# 4_cyber60-mxhs_periferals.net
KiCad netlist of a schematic drawn in Altium Designer
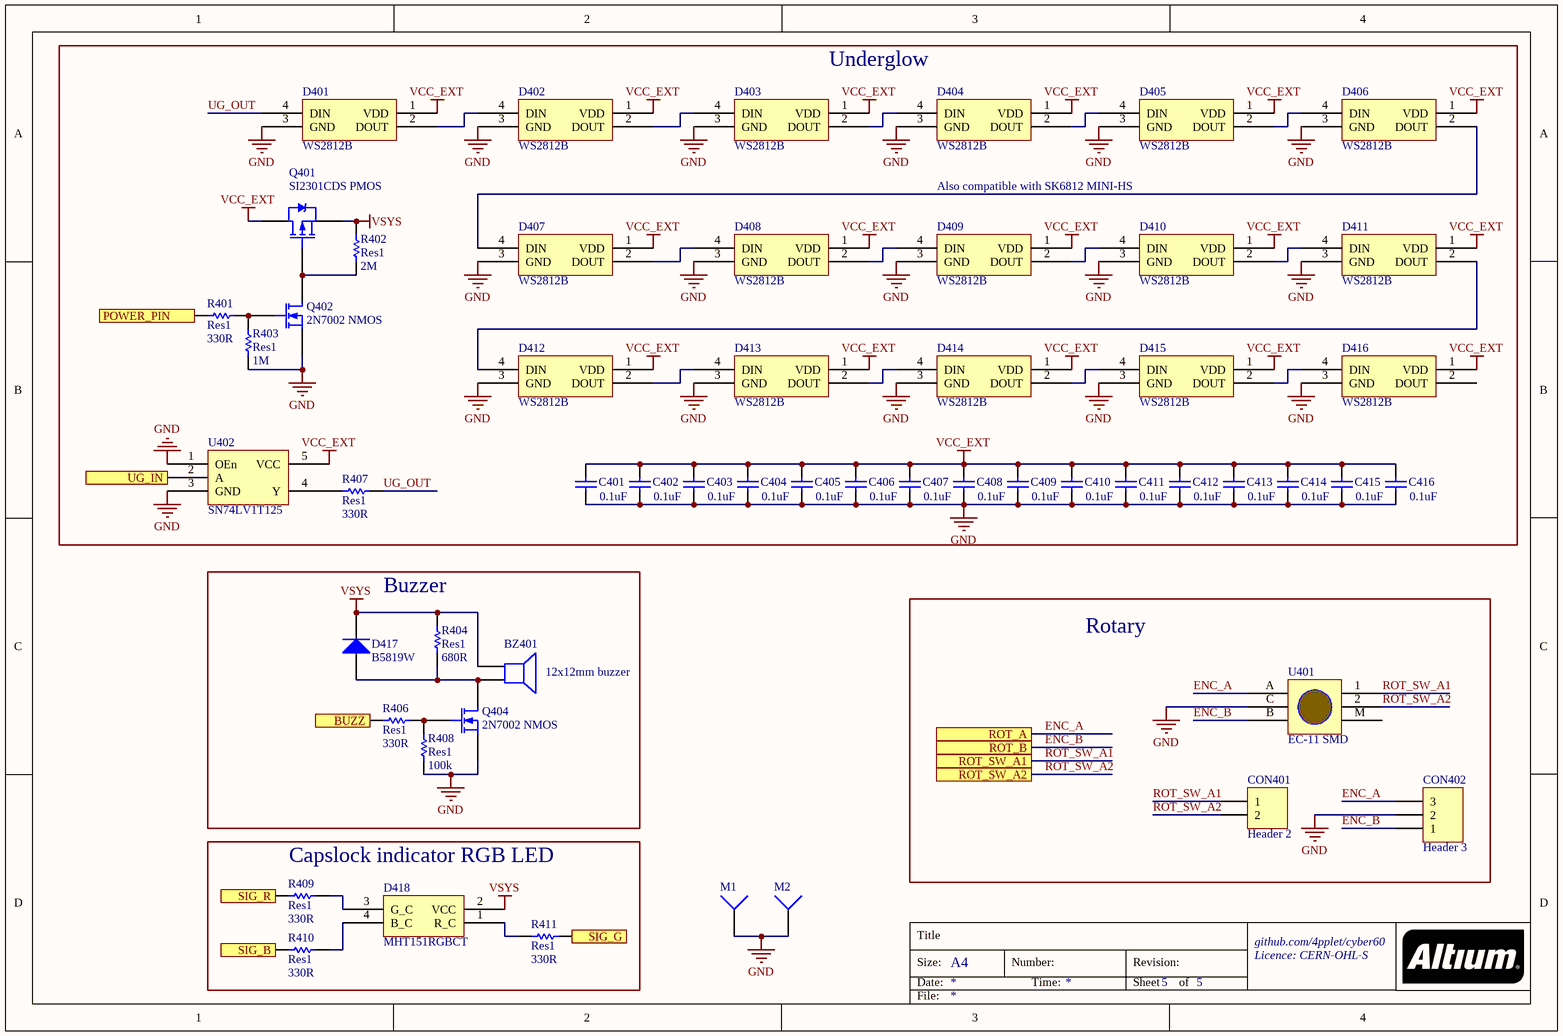
[diagram p0: 4_cyber60-mxhs_periferals.SchDoc]

(export (version "E")
  (design (tool "Eeschema 10.0.6"))
  (components
    (comp (ref "BZ401")
      (value "12x12mm buzzer")
      (footprint "buzzer 12x12")
      (description "Loudspeaker")
      (fields (field (name "LCSC PART #") "C409829") (field (name "MRF.PART") "YS-SBZ1230"))
      (libsource (lib "Miscellaneous Devices") (part "Speaker"))
    )
    (comp (ref "C401")
      (value "0.1uF")
      (footprint "C0603[1608]")
      (description "Capacitor")
      (fields (field (name "MFG") "KEMET") (field (name "LCSC PART #") "C14663"))
      (libsource (lib "Miscellaneous Devices") (part "Cap"))
    )
    (comp (ref "C402")
      (value "0.1uF")
      (footprint "C0603[1608]")
      (description "Capacitor")
      (fields (field (name "MFG") "KEMET") (field (name "LCSC PART #") "C14663"))
      (libsource (lib "Miscellaneous Devices") (part "Cap"))
    )
    (comp (ref "C403")
      (value "0.1uF")
      (footprint "C0603[1608]")
      (description "Capacitor")
      (fields (field (name "MFG") "KEMET") (field (name "LCSC PART #") "C14663"))
      (libsource (lib "Miscellaneous Devices") (part "Cap"))
    )
    (comp (ref "C404")
      (value "0.1uF")
      (footprint "C0603[1608]")
      (description "Capacitor")
      (fields (field (name "MFG") "KEMET") (field (name "LCSC PART #") "C14663"))
      (libsource (lib "Miscellaneous Devices") (part "Cap"))
    )
    (comp (ref "C405")
      (value "0.1uF")
      (footprint "C0603[1608]")
      (description "Capacitor")
      (fields (field (name "MFG") "KEMET") (field (name "LCSC PART #") "C14663"))
      (libsource (lib "Miscellaneous Devices") (part "Cap"))
    )
    (comp (ref "C406")
      (value "0.1uF")
      (footprint "C0603[1608]")
      (description "Capacitor")
      (fields (field (name "MFG") "KEMET") (field (name "LCSC PART #") "C14663"))
      (libsource (lib "Miscellaneous Devices") (part "Cap"))
    )
    (comp (ref "C407")
      (value "0.1uF")
      (footprint "C0603[1608]")
      (description "Capacitor")
      (fields (field (name "MFG") "KEMET") (field (name "LCSC PART #") "C14663"))
      (libsource (lib "Miscellaneous Devices") (part "Cap"))
    )
    (comp (ref "C408")
      (value "0.1uF")
      (footprint "C0603[1608]")
      (description "Capacitor")
      (fields (field (name "MFG") "KEMET") (field (name "LCSC PART #") "C14663"))
      (libsource (lib "Miscellaneous Devices") (part "Cap"))
    )
    (comp (ref "C409")
      (value "0.1uF")
      (footprint "C0603[1608]")
      (description "Capacitor")
      (fields (field (name "MFG") "KEMET") (field (name "LCSC PART #") "C14663"))
      (libsource (lib "Miscellaneous Devices") (part "Cap"))
    )
    (comp (ref "C410")
      (value "0.1uF")
      (footprint "C0603[1608]")
      (description "Capacitor")
      (fields (field (name "MFG") "KEMET") (field (name "LCSC PART #") "C14663"))
      (libsource (lib "Miscellaneous Devices") (part "Cap"))
    )
    (comp (ref "C411")
      (value "0.1uF")
      (footprint "C0603[1608]")
      (description "Capacitor")
      (fields (field (name "MFG") "KEMET") (field (name "LCSC PART #") "C14663"))
      (libsource (lib "Miscellaneous Devices") (part "Cap"))
    )
    (comp (ref "C412")
      (value "0.1uF")
      (footprint "C0603[1608]")
      (description "Capacitor")
      (fields (field (name "MFG") "KEMET") (field (name "LCSC PART #") "C14663"))
      (libsource (lib "Miscellaneous Devices") (part "Cap"))
    )
    (comp (ref "C413")
      (value "0.1uF")
      (footprint "C0603[1608]")
      (description "Capacitor")
      (fields (field (name "MFG") "KEMET") (field (name "LCSC PART #") "C14663"))
      (libsource (lib "Miscellaneous Devices") (part "Cap"))
    )
    (comp (ref "C414")
      (value "0.1uF")
      (footprint "C0603[1608]")
      (description "Capacitor")
      (fields (field (name "MFG") "KEMET") (field (name "LCSC PART #") "C14663"))
      (libsource (lib "Miscellaneous Devices") (part "Cap"))
    )
    (comp (ref "C415")
      (value "0.1uF")
      (footprint "C0603[1608]")
      (description "Capacitor")
      (fields (field (name "MFG") "KEMET") (field (name "LCSC PART #") "C14663"))
      (libsource (lib "Miscellaneous Devices") (part "Cap"))
    )
    (comp (ref "C416")
      (value "0.1uF")
      (footprint "C0603[1608]")
      (description "Capacitor")
      (fields (field (name "MFG") "KEMET") (field (name "LCSC PART #") "C14663"))
      (libsource (lib "Miscellaneous Devices") (part "Cap"))
    )
    (comp (ref "CON401")
      (value "Header 2")
      (footprint "HDR1X2")
      (description "Header, 2-Pin")
      (libsource (lib "Miscellaneous Connectors") (part "Header 2"))
    )
    (comp (ref "CON402")
      (value "Header 3")
      (footprint "HDR1X3")
      (description "Header, 3-Pin")
      (libsource (lib "Miscellaneous Connectors") (part "Header 3"))
    )
    (comp (ref "D401")
      (value "WS2812B")
      (footprint "WS2812B - 2020")
      (fields (field (name "LCSC PART #") "C965556") (field (name "MRF.PART") "WS2812C-2020"))
      (libsource (lib "Keebs") (part "WS2812B"))
    )
    (comp (ref "D402")
      (value "WS2812B")
      (footprint "WS2812B - 2020")
      (fields (field (name "LCSC PART #") "C965556") (field (name "MRF.PART") "WS2812C-2020"))
      (libsource (lib "Keebs") (part "WS2812B"))
    )
    (comp (ref "D403")
      (value "WS2812B")
      (footprint "WS2812B - 2020")
      (fields (field (name "LCSC PART #") "C965556") (field (name "MRF.PART") "WS2812C-2020"))
      (libsource (lib "Keebs") (part "WS2812B"))
    )
    (comp (ref "D404")
      (value "WS2812B")
      (footprint "WS2812B - 2020")
      (fields (field (name "LCSC PART #") "C965556") (field (name "MRF.PART") "WS2812C-2020"))
      (libsource (lib "Keebs") (part "WS2812B"))
    )
    (comp (ref "D405")
      (value "WS2812B")
      (footprint "WS2812B - 2020")
      (fields (field (name "LCSC PART #") "C965556") (field (name "MRF.PART") "WS2812C-2020"))
      (libsource (lib "Keebs") (part "WS2812B"))
    )
    (comp (ref "D406")
      (value "WS2812B")
      (footprint "WS2812B - 2020")
      (fields (field (name "LCSC PART #") "C965556") (field (name "MRF.PART") "WS2812C-2020"))
      (libsource (lib "Keebs") (part "WS2812B"))
    )
    (comp (ref "D407")
      (value "WS2812B")
      (footprint "WS2812B - 2020")
      (fields (field (name "LCSC PART #") "C965556") (field (name "MRF.PART") "WS2812C-2020"))
      (libsource (lib "Keebs") (part "WS2812B"))
    )
    (comp (ref "D408")
      (value "WS2812B")
      (footprint "WS2812B - 2020")
      (fields (field (name "LCSC PART #") "C965556") (field (name "MRF.PART") "WS2812C-2020"))
      (libsource (lib "Keebs") (part "WS2812B"))
    )
    (comp (ref "D409")
      (value "WS2812B")
      (footprint "WS2812B - 2020")
      (fields (field (name "LCSC PART #") "C965556") (field (name "MRF.PART") "WS2812C-2020"))
      (libsource (lib "Keebs") (part "WS2812B"))
    )
    (comp (ref "D410")
      (value "WS2812B")
      (footprint "WS2812B - 2020")
      (fields (field (name "LCSC PART #") "C965556") (field (name "MRF.PART") "WS2812C-2020"))
      (libsource (lib "Keebs") (part "WS2812B"))
    )
    (comp (ref "D411")
      (value "WS2812B")
      (footprint "WS2812B - 2020")
      (fields (field (name "LCSC PART #") "C965556") (field (name "MRF.PART") "WS2812C-2020"))
      (libsource (lib "Keebs") (part "WS2812B"))
    )
    (comp (ref "D412")
      (value "WS2812B")
      (footprint "WS2812B - 2020")
      (fields (field (name "LCSC PART #") "C965556") (field (name "MRF.PART") "WS2812C-2020"))
      (libsource (lib "Keebs") (part "WS2812B"))
    )
    (comp (ref "D413")
      (value "WS2812B")
      (footprint "WS2812B - 2020")
      (fields (field (name "LCSC PART #") "C965556") (field (name "MRF.PART") "WS2812C-2020"))
      (libsource (lib "Keebs") (part "WS2812B"))
    )
    (comp (ref "D414")
      (value "WS2812B")
      (footprint "WS2812B - 2020")
      (fields (field (name "LCSC PART #") "C965556") (field (name "MRF.PART") "WS2812C-2020"))
      (libsource (lib "Keebs") (part "WS2812B"))
    )
    (comp (ref "D415")
      (value "WS2812B")
      (footprint "WS2812B - 2020")
      (fields (field (name "LCSC PART #") "C965556") (field (name "MRF.PART") "WS2812C-2020"))
      (libsource (lib "Keebs") (part "WS2812B"))
    )
    (comp (ref "D416")
      (value "WS2812B")
      (footprint "WS2812B - 2020")
      (fields (field (name "LCSC PART #") "C965556") (field (name "MRF.PART") "WS2812C-2020"))
      (libsource (lib "Keebs") (part "WS2812B"))
    )
    (comp (ref "D417")
      (value "B5819W")
      (footprint "SOD-123")
      (description "Default Diode")
      (fields (field (name "LCSC PART #") "C8598"))
      (libsource (lib "Miscellaneous Devices") (part "Diode"))
    )
    (comp (ref "D418")
      (value "MHT151RGBCT")
      (footprint "MHT151RGBCT")
      (fields (field (name "LCSC PART #") "C2802677") (field (name "MRF.PART") "E6CC1205RGBC3UDA"))
      (libsource (lib "Keebs") (part "MHT151RGBCT"))
    )
    (comp (ref "M1")
      (value "Socket")
      (footprint "mounting_hole")
      (fields (field (name "PUBLISHER") "Altium Limited"))
      (libsource (lib "Miscellaneous Connectors") (part "Socket"))
    )
    (comp (ref "M2")
      (value "Socket")
      (footprint "mounting_hole")
      (fields (field (name "PUBLISHER") "Altium Limited"))
      (libsource (lib "Miscellaneous Connectors") (part "Socket"))
    )
    (comp (ref "Q401")
      (value "SI2301CDS PMOS")
      (footprint "SOT-23-3")
      (description "P-Channel Power MOSFET")
      (fields (field (name "MRF.PART") "SI2301CDS-T1-GE3") (field (name "LCSC PART #") "C10487"))
      (libsource (lib "Miscellaneous Devices") (part "PMOS-2"))
    )
    (comp (ref "Q402")
      (value "2N7002 NMOS")
      (footprint "SOT-23-3")
      (description "N-Channel MOSFET")
      (fields (field (name "LCSC PART #") "C8545") (field (name "MRF.PART") "2N7002"))
      (libsource (lib "Miscellaneous Devices") (part "MOSFET-N"))
    )
    (comp (ref "Q404")
      (value "2N7002 NMOS")
      (footprint "SOT-23-3")
      (description "N-Channel MOSFET")
      (fields (field (name "LCSC PART #") "C8545") (field (name "MRF.PART") "2N7002"))
      (libsource (lib "Miscellaneous Devices") (part "MOSFET-N"))
    )
    (comp (ref "R401")
      (value "Res1")
      (footprint "R0603[1608]")
      (description "Resistor")
      (fields
        (field (name "ALTIUM_VALUE") "330R")
        (field (name "LCSC PART #") "C23138")
        (field (name "MRF.PART") "0603WAF3300T5E")
      )
      (libsource (lib "Miscellaneous Devices") (part "Res1"))
    )
    (comp (ref "R402")
      (value "Res1")
      (footprint "R0603[1608]")
      (description "Resistor")
      (fields
        (field (name "ALTIUM_VALUE") "2M")
        (field (name "MRF.PART") "0603WAF2004T5E")
        (field (name "LCSC PART #") "C22976")
      )
      (libsource (lib "Miscellaneous Devices") (part "Res1"))
    )
    (comp (ref "R403")
      (value "Res1")
      (footprint "R0603[1608]")
      (description "Resistor")
      (fields
        (field (name "ALTIUM_VALUE") "1M")
        (field (name "MRF.PART") "0603WAF1004T5E")
        (field (name "LCSC PART #") "C22935")
      )
      (libsource (lib "Miscellaneous Devices") (part "Res1"))
    )
    (comp (ref "R404")
      (value "Res1")
      (footprint "R0603[1608]")
      (description "Resistor")
      (fields
        (field (name "ALTIUM_VALUE") "680R")
        (field (name "MRF.PART") "0603WAF6800T5E")
        (field (name "LCSC PART #") "C23228")
      )
      (libsource (lib "Miscellaneous Devices") (part "Res1"))
    )
    (comp (ref "R406")
      (value "Res1")
      (footprint "R0603[1608]")
      (description "Resistor")
      (fields
        (field (name "ALTIUM_VALUE") "330R")
        (field (name "LCSC PART #") "C23138")
        (field (name "MRF.PART") "0603WAF3300T5E")
      )
      (libsource (lib "Miscellaneous Devices") (part "Res1"))
    )
    (comp (ref "R407")
      (value "Res1")
      (footprint "R0603[1608]")
      (description "Resistor")
      (fields
        (field (name "ALTIUM_VALUE") "330R")
        (field (name "LCSC PART #") "C23138")
        (field (name "MRF.PART") "0603WAF3300T5E")
      )
      (libsource (lib "Miscellaneous Devices") (part "Res1"))
    )
    (comp (ref "R408")
      (value "Res1")
      (footprint "R0603[1608]")
      (description "Resistor")
      (fields
        (field (name "ALTIUM_VALUE") "100k")
        (field (name "MRF.PART") "0603WAF1003T5E")
        (field (name "LCSC PART #") "C25803")
      )
      (libsource (lib "Miscellaneous Devices") (part "Res1"))
    )
    (comp (ref "R409")
      (value "Res1")
      (footprint "R0603[1608]")
      (description "Resistor")
      (fields
        (field (name "ALTIUM_VALUE") "330R")
        (field (name "LCSC PART #") "C23138")
        (field (name "MRF.PART") "0603WAF3300T5E")
      )
      (libsource (lib "Miscellaneous Devices") (part "Res1"))
    )
    (comp (ref "R410")
      (value "Res1")
      (footprint "R0603[1608]")
      (description "Resistor")
      (fields
        (field (name "ALTIUM_VALUE") "330R")
        (field (name "LCSC PART #") "C23138")
        (field (name "MRF.PART") "0603WAF3300T5E")
      )
      (libsource (lib "Miscellaneous Devices") (part "Res1"))
    )
    (comp (ref "R411")
      (value "Res1")
      (footprint "R0603[1608]")
      (description "Resistor")
      (fields
        (field (name "ALTIUM_VALUE") "330R")
        (field (name "LCSC PART #") "C23138")
        (field (name "MRF.PART") "0603WAF3300T5E")
      )
      (libsource (lib "Miscellaneous Devices") (part "Res1"))
    )
    (comp (ref "U401") (value "EC-11 SMD") (footprint "EC11-SMD") (libsource (lib "Keebs") (part "EC-11")))
    (comp (ref "U402")
      (value "SN74LV1T125")
      (footprint "SOT-23-5")
      (description "SN74LV1T125 or SN74LV1T34. Connect OE to GND")
      (fields (field (name "LCSC PART #") "C473338") (field (name "MRF.PART") "SN74LV1T125DBVR"))
      (libsource (lib "Keebs") (part "SN74LV1T125"))
    )
  )
  (nets
    (net (code "1") (name "/BUZZ") (class "Default")
      (node (ref "R406") (pin "2") (pinfunction "2_2") (pintype "passive"))
    )
    (net (code "2") (name "/ENC_A") (class "Default")
      (node (ref "CON402") (pin "3") (pinfunction "3_3") (pintype "passive"))
      (node (ref "U401") (pin "A") (pinfunction "B_A") (pintype "passive"))
    )
    (net (code "3") (name "/ENC_B") (class "Default")
      (node (ref "CON402") (pin "1") (pinfunction "1_1") (pintype "passive"))
      (node (ref "U401") (pin "B") (pinfunction "B_B") (pintype "passive"))
    )
    (net (code "4") (name "/POWER_PIN") (class "Default")
      (node (ref "R401") (pin "1") (pinfunction "1_1") (pintype "passive"))
    )
    (net (code "5") (name "/ROT_SW_A1") (class "Default")
      (node (ref "CON401") (pin "1") (pinfunction "1_1") (pintype "passive"))
      (node (ref "U401") (pin "1") (pinfunction "1_1") (pintype "passive"))
    )
    (net (code "6") (name "/ROT_SW_A2") (class "Default")
      (node (ref "CON401") (pin "2") (pinfunction "2_2") (pintype "passive"))
      (node (ref "U401") (pin "2") (pinfunction "2_2") (pintype "passive"))
    )
    (net (code "7") (name "/SIG_B") (class "Default")
      (node (ref "R410") (pin "2") (pinfunction "2_2") (pintype "passive"))
    )
    (net (code "8") (name "/SIG_G") (class "Default")
      (node (ref "R411") (pin "1") (pinfunction "1_1") (pintype "passive"))
    )
    (net (code "9") (name "/SIG_R") (class "Default")
      (node (ref "R409") (pin "2") (pinfunction "2_2") (pintype "passive"))
    )
    (net (code "10") (name "/UG_IN") (class "Default")
      (node (ref "U402") (pin "2") (pinfunction "A_2") (pintype "passive"))
    )
    (net (code "11") (name "/UG_OUT") (class "Default")
      (node (ref "D401") (pin "4") (pinfunction "DIN_4") (pintype "passive"))
      (node (ref "R407") (pin "1") (pinfunction "1_1") (pintype "passive"))
    )
    (net (code "12") (name "GND") (class "Default")
      (node (ref "C401") (pin "1") (pinfunction "1_1") (pintype "passive"))
      (node (ref "C402") (pin "1") (pinfunction "1_1") (pintype "passive"))
      (node (ref "C403") (pin "1") (pinfunction "1_1") (pintype "passive"))
      (node (ref "C404") (pin "1") (pinfunction "1_1") (pintype "passive"))
      (node (ref "C405") (pin "1") (pinfunction "1_1") (pintype "passive"))
      (node (ref "C406") (pin "1") (pinfunction "1_1") (pintype "passive"))
      (node (ref "C407") (pin "1") (pinfunction "1_1") (pintype "passive"))
      (node (ref "C408") (pin "1") (pinfunction "1_1") (pintype "passive"))
      (node (ref "C409") (pin "1") (pinfunction "1_1") (pintype "passive"))
      (node (ref "C410") (pin "1") (pinfunction "1_1") (pintype "passive"))
      (node (ref "C411") (pin "1") (pinfunction "1_1") (pintype "passive"))
      (node (ref "C412") (pin "1") (pinfunction "1_1") (pintype "passive"))
      (node (ref "C413") (pin "1") (pinfunction "1_1") (pintype "passive"))
      (node (ref "C414") (pin "1") (pinfunction "1_1") (pintype "passive"))
      (node (ref "C415") (pin "1") (pinfunction "1_1") (pintype "passive"))
      (node (ref "C416") (pin "1") (pinfunction "1_1") (pintype "passive"))
      (node (ref "CON402") (pin "2") (pinfunction "2_2") (pintype "passive"))
      (node (ref "D401") (pin "3") (pinfunction "GND_3") (pintype "passive"))
      (node (ref "D402") (pin "3") (pinfunction "GND_3") (pintype "passive"))
      (node (ref "D403") (pin "3") (pinfunction "GND_3") (pintype "passive"))
      (node (ref "D404") (pin "3") (pinfunction "GND_3") (pintype "passive"))
      (node (ref "D405") (pin "3") (pinfunction "GND_3") (pintype "passive"))
      (node (ref "D406") (pin "3") (pinfunction "GND_3") (pintype "passive"))
      (node (ref "D407") (pin "3") (pinfunction "GND_3") (pintype "passive"))
      (node (ref "D408") (pin "3") (pinfunction "GND_3") (pintype "passive"))
      (node (ref "D409") (pin "3") (pinfunction "GND_3") (pintype "passive"))
      (node (ref "D410") (pin "3") (pinfunction "GND_3") (pintype "passive"))
      (node (ref "D411") (pin "3") (pinfunction "GND_3") (pintype "passive"))
      (node (ref "D412") (pin "3") (pinfunction "GND_3") (pintype "passive"))
      (node (ref "D413") (pin "3") (pinfunction "GND_3") (pintype "passive"))
      (node (ref "D414") (pin "3") (pinfunction "GND_3") (pintype "passive"))
      (node (ref "D415") (pin "3") (pinfunction "GND_3") (pintype "passive"))
      (node (ref "D416") (pin "3") (pinfunction "GND_3") (pintype "passive"))
      (node (ref "M1") (pin "1") (pinfunction "1_1") (pintype "passive"))
      (node (ref "M2") (pin "1") (pinfunction "1_1") (pintype "passive"))
      (node (ref "Q402") (pin "2") (pinfunction "S_2") (pintype "passive"))
      (node (ref "Q404") (pin "2") (pinfunction "S_2") (pintype "passive"))
      (node (ref "R403") (pin "2") (pinfunction "2_2") (pintype "passive"))
      (node (ref "R408") (pin "2") (pinfunction "2_2") (pintype "passive"))
      (node (ref "U401") (pin "C") (pinfunction "C_C") (pintype "passive"))
      (node (ref "U402") (pin "1") (pinfunction "OEn_1") (pintype "passive"))
      (node (ref "U402") (pin "3") (pinfunction "GND_3") (pintype "passive"))
    )
    (net (code "13") (name "Net-(D401-DOUT)") (class "Default")
      (node (ref "D401") (pin "2") (pinfunction "DOUT_2") (pintype "passive"))
      (node (ref "D402") (pin "4") (pinfunction "DIN_4") (pintype "passive"))
    )
    (net (code "14") (name "Net-(D402-DOUT)") (class "Default")
      (node (ref "D402") (pin "2") (pinfunction "DOUT_2") (pintype "passive"))
      (node (ref "D403") (pin "4") (pinfunction "DIN_4") (pintype "passive"))
    )
    (net (code "15") (name "Net-(D403-DOUT)") (class "Default")
      (node (ref "D403") (pin "2") (pinfunction "DOUT_2") (pintype "passive"))
      (node (ref "D404") (pin "4") (pinfunction "DIN_4") (pintype "passive"))
    )
    (net (code "16") (name "Net-(D404-DOUT)") (class "Default")
      (node (ref "D404") (pin "2") (pinfunction "DOUT_2") (pintype "passive"))
      (node (ref "D405") (pin "4") (pinfunction "DIN_4") (pintype "passive"))
    )
    (net (code "17") (name "Net-(D405-DOUT)") (class "Default")
      (node (ref "D405") (pin "2") (pinfunction "DOUT_2") (pintype "passive"))
      (node (ref "D406") (pin "4") (pinfunction "DIN_4") (pintype "passive"))
    )
    (net (code "18") (name "Net-(D406-DOUT)") (class "Default")
      (node (ref "D406") (pin "2") (pinfunction "DOUT_2") (pintype "passive"))
      (node (ref "D407") (pin "4") (pinfunction "DIN_4") (pintype "passive"))
    )
    (net (code "19") (name "Net-(D407-DOUT)") (class "Default")
      (node (ref "D407") (pin "2") (pinfunction "DOUT_2") (pintype "passive"))
      (node (ref "D408") (pin "4") (pinfunction "DIN_4") (pintype "passive"))
    )
    (net (code "20") (name "Net-(D408-DOUT)") (class "Default")
      (node (ref "D408") (pin "2") (pinfunction "DOUT_2") (pintype "passive"))
      (node (ref "D409") (pin "4") (pinfunction "DIN_4") (pintype "passive"))
    )
    (net (code "21") (name "Net-(D409-DOUT)") (class "Default")
      (node (ref "D409") (pin "2") (pinfunction "DOUT_2") (pintype "passive"))
      (node (ref "D410") (pin "4") (pinfunction "DIN_4") (pintype "passive"))
    )
    (net (code "22") (name "Net-(D410-DOUT)") (class "Default")
      (node (ref "D410") (pin "2") (pinfunction "DOUT_2") (pintype "passive"))
      (node (ref "D411") (pin "4") (pinfunction "DIN_4") (pintype "passive"))
    )
    (net (code "23") (name "Net-(D411-DOUT)") (class "Default")
      (node (ref "D411") (pin "2") (pinfunction "DOUT_2") (pintype "passive"))
      (node (ref "D412") (pin "4") (pinfunction "DIN_4") (pintype "passive"))
    )
    (net (code "24") (name "Net-(D412-DOUT)") (class "Default")
      (node (ref "D412") (pin "2") (pinfunction "DOUT_2") (pintype "passive"))
      (node (ref "D413") (pin "4") (pinfunction "DIN_4") (pintype "passive"))
    )
    (net (code "25") (name "Net-(D413-DOUT)") (class "Default")
      (node (ref "D413") (pin "2") (pinfunction "DOUT_2") (pintype "passive"))
      (node (ref "D414") (pin "4") (pinfunction "DIN_4") (pintype "passive"))
    )
    (net (code "26") (name "Net-(D414-DOUT)") (class "Default")
      (node (ref "D414") (pin "2") (pinfunction "DOUT_2") (pintype "passive"))
      (node (ref "D415") (pin "4") (pinfunction "DIN_4") (pintype "passive"))
    )
    (net (code "27") (name "Net-(D415-DOUT)") (class "Default")
      (node (ref "D415") (pin "2") (pinfunction "DOUT_2") (pintype "passive"))
      (node (ref "D416") (pin "4") (pinfunction "DIN_4") (pintype "passive"))
    )
    (net (code "28") (name "Net-(D417-A)") (class "Default")
      (node (ref "BZ401") (pin "2") (pinfunction "2_2") (pintype "passive"))
      (node (ref "D417") (pin "1") (pinfunction "A_1") (pintype "passive"))
      (node (ref "Q404") (pin "3") (pinfunction "D_3") (pintype "passive"))
      (node (ref "R404") (pin "2") (pinfunction "2_2") (pintype "passive"))
    )
    (net (code "29") (name "Net-(D418-B_C)") (class "Default")
      (node (ref "D418") (pin "4") (pinfunction "B_C_4") (pintype "passive"))
      (node (ref "R410") (pin "1") (pinfunction "1_1") (pintype "passive"))
    )
    (net (code "30") (name "Net-(D418-G_C)") (class "Default")
      (node (ref "D418") (pin "3") (pinfunction "G_C_3") (pintype "passive"))
      (node (ref "R409") (pin "1") (pinfunction "1_1") (pintype "passive"))
    )
    (net (code "31") (name "Net-(D418-R_C)") (class "Default")
      (node (ref "D418") (pin "1") (pinfunction "R_C_1") (pintype "passive"))
      (node (ref "R411") (pin "2") (pinfunction "2_2") (pintype "passive"))
    )
    (net (code "32") (name "Net-(Q401-G)") (class "Default")
      (node (ref "Q401") (pin "1") (pinfunction "G_1") (pintype "passive"))
      (node (ref "Q402") (pin "3") (pinfunction "D_3") (pintype "passive"))
      (node (ref "R402") (pin "1") (pinfunction "1_1") (pintype "passive"))
    )
    (net (code "33") (name "Net-(Q402-G)") (class "Default")
      (node (ref "Q402") (pin "1") (pinfunction "G_1") (pintype "passive"))
      (node (ref "R401") (pin "2") (pinfunction "2_2") (pintype "passive"))
      (node (ref "R403") (pin "1") (pinfunction "1_1") (pintype "passive"))
    )
    (net (code "34") (name "Net-(Q404-G)") (class "Default")
      (node (ref "Q404") (pin "1") (pinfunction "G_1") (pintype "passive"))
      (node (ref "R406") (pin "1") (pinfunction "1_1") (pintype "passive"))
      (node (ref "R408") (pin "1") (pinfunction "1_1") (pintype "passive"))
    )
    (net (code "35") (name "Net-(U402-Y)") (class "Default")
      (node (ref "R407") (pin "2") (pinfunction "2_2") (pintype "passive"))
      (node (ref "U402") (pin "4") (pinfunction "Y_4") (pintype "passive"))
    )
    (net (code "36") (name "VCC_EXT") (class "Default")
      (node (ref "C401") (pin "2") (pinfunction "2_2") (pintype "passive"))
      (node (ref "C402") (pin "2") (pinfunction "2_2") (pintype "passive"))
      (node (ref "C403") (pin "2") (pinfunction "2_2") (pintype "passive"))
      (node (ref "C404") (pin "2") (pinfunction "2_2") (pintype "passive"))
      (node (ref "C405") (pin "2") (pinfunction "2_2") (pintype "passive"))
      (node (ref "C406") (pin "2") (pinfunction "2_2") (pintype "passive"))
      (node (ref "C407") (pin "2") (pinfunction "2_2") (pintype "passive"))
      (node (ref "C408") (pin "2") (pinfunction "2_2") (pintype "passive"))
      (node (ref "C409") (pin "2") (pinfunction "2_2") (pintype "passive"))
      (node (ref "C410") (pin "2") (pinfunction "2_2") (pintype "passive"))
      (node (ref "C411") (pin "2") (pinfunction "2_2") (pintype "passive"))
      (node (ref "C412") (pin "2") (pinfunction "2_2") (pintype "passive"))
      (node (ref "C413") (pin "2") (pinfunction "2_2") (pintype "passive"))
      (node (ref "C414") (pin "2") (pinfunction "2_2") (pintype "passive"))
      (node (ref "C415") (pin "2") (pinfunction "2_2") (pintype "passive"))
      (node (ref "C416") (pin "2") (pinfunction "2_2") (pintype "passive"))
      (node (ref "D401") (pin "1") (pinfunction "VDD_1") (pintype "passive"))
      (node (ref "D402") (pin "1") (pinfunction "VDD_1") (pintype "passive"))
      (node (ref "D403") (pin "1") (pinfunction "VDD_1") (pintype "passive"))
      (node (ref "D404") (pin "1") (pinfunction "VDD_1") (pintype "passive"))
      (node (ref "D405") (pin "1") (pinfunction "VDD_1") (pintype "passive"))
      (node (ref "D406") (pin "1") (pinfunction "VDD_1") (pintype "passive"))
      (node (ref "D407") (pin "1") (pinfunction "VDD_1") (pintype "passive"))
      (node (ref "D408") (pin "1") (pinfunction "VDD_1") (pintype "passive"))
      (node (ref "D409") (pin "1") (pinfunction "VDD_1") (pintype "passive"))
      (node (ref "D410") (pin "1") (pinfunction "VDD_1") (pintype "passive"))
      (node (ref "D411") (pin "1") (pinfunction "VDD_1") (pintype "passive"))
      (node (ref "D412") (pin "1") (pinfunction "VDD_1") (pintype "passive"))
      (node (ref "D413") (pin "1") (pinfunction "VDD_1") (pintype "passive"))
      (node (ref "D414") (pin "1") (pinfunction "VDD_1") (pintype "passive"))
      (node (ref "D415") (pin "1") (pinfunction "VDD_1") (pintype "passive"))
      (node (ref "D416") (pin "1") (pinfunction "VDD_1") (pintype "passive"))
      (node (ref "Q401") (pin "3") (pinfunction "D_3") (pintype "passive"))
      (node (ref "U402") (pin "5") (pinfunction "VCC_5") (pintype "passive"))
    )
    (net (code "37") (name "VSYS") (class "Default")
      (node (ref "BZ401") (pin "1") (pinfunction "1_1") (pintype "passive"))
      (node (ref "D417") (pin "2") (pinfunction "K_2") (pintype "passive"))
      (node (ref "D418") (pin "2") (pinfunction "VCC_2") (pintype "passive"))
      (node (ref "Q401") (pin "2") (pinfunction "S_2") (pintype "passive"))
      (node (ref "R402") (pin "2") (pinfunction "2_2") (pintype "passive"))
      (node (ref "R404") (pin "1") (pinfunction "1_1") (pintype "passive"))
    )
    (net (code "38") (name "unconnected-(D416-DOUT-Pad2)") (class "Default")
      (node (ref "D416") (pin "2") (pinfunction "DOUT_2") (pintype "passive"))
    )
    (net (code "39") (name "unconnected-(U401-PadM)") (class "Default")
      (node (ref "U401") (pin "M") (pinfunction "M_M") (pintype "passive"))
    )
  )
)
